# DMX_dimmer.net
KiCad netlist of a schematic drawn in EAGLE
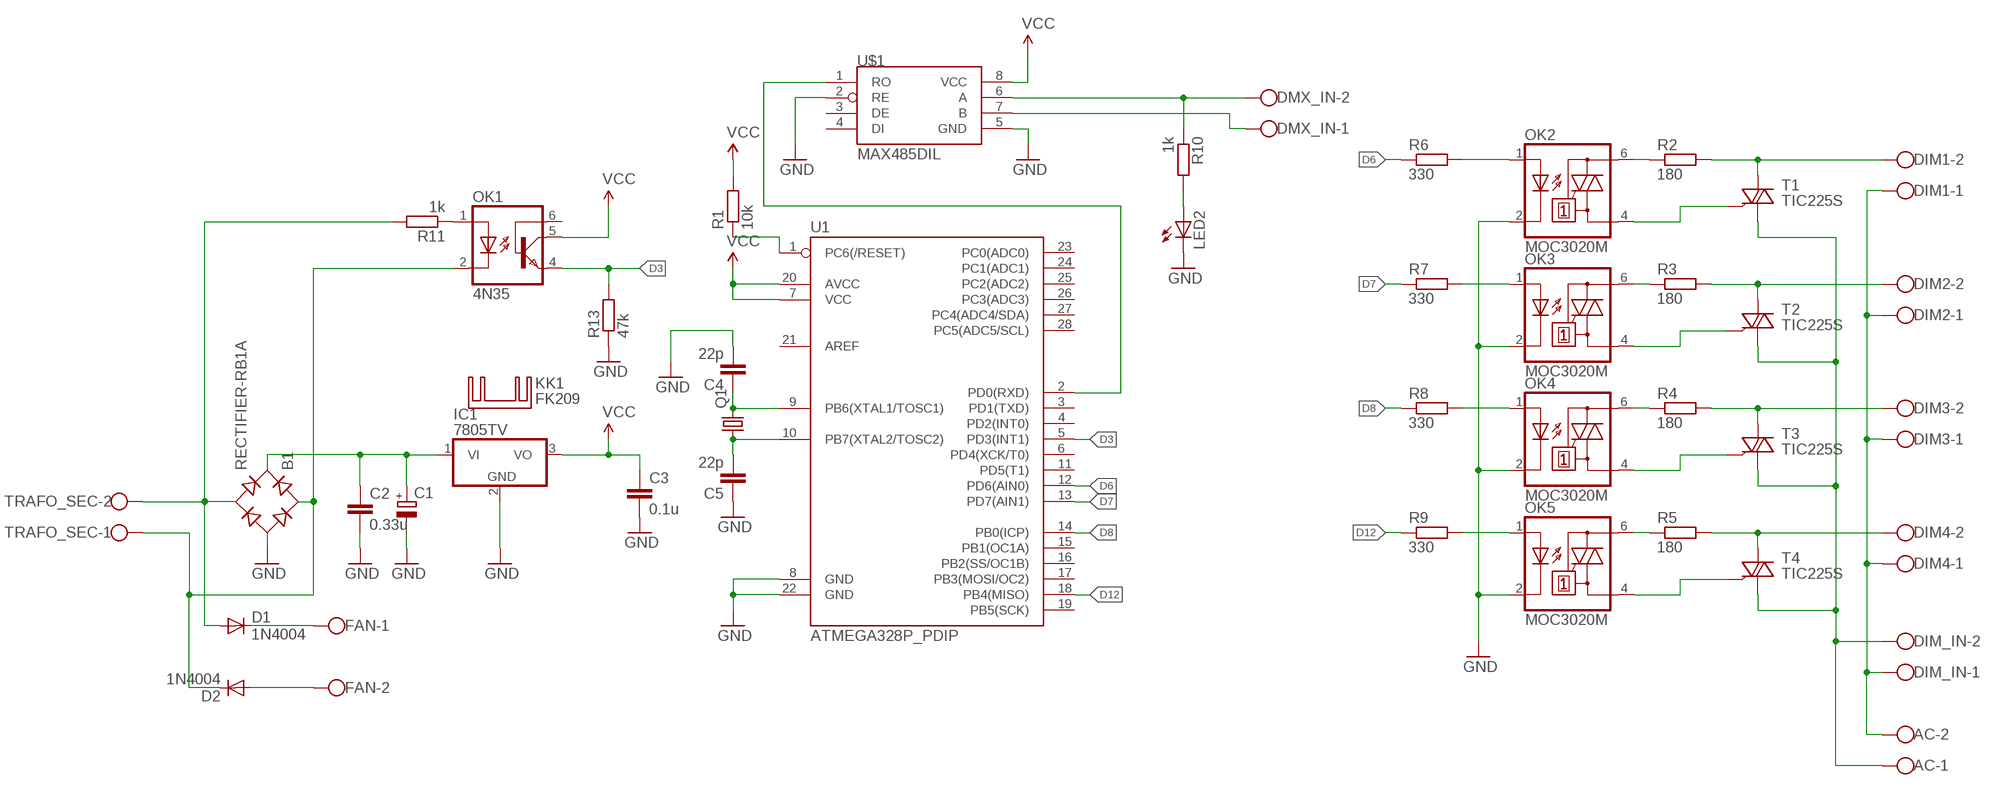
[diagram p0: schematic, sheet 1]

(export (version "E")
  (design (tool "Eeschema 10.0.6"))
  (components
    (comp (ref "AC")
      (value "W237-102")
      (footprint "eagle-import:W237-102")
      (fields (field (name "MPN") "237-102"))
      (libsource (lib "eagle-import") (part "W237-102"))
    )
    (comp (ref "B1")
      (value "RECTIFIER-RB1A")
      (footprint "eagle-import:RB1A")
      (libsource (lib "eagle-import") (part "RECTIFIER-RB1A"))
    )
    (comp (ref "C1")
      (value "CPOL-EUE5-10.5")
      (footprint "eagle-import:E5-10,5")
      (libsource (lib "eagle-import") (part "CPOL-EUE5-10.5"))
    )
    (comp (ref "C2")
      (value "0.33u")
      (footprint "eagle-import:C050-024X044")
      (libsource (lib "eagle-import") (part "C-EU050-024X044"))
    )
    (comp (ref "C3")
      (value "0.1u")
      (footprint "eagle-import:C050-024X044")
      (libsource (lib "eagle-import") (part "C-EU050-024X044"))
    )
    (comp (ref "C4")
      (value "22p")
      (footprint "eagle-import:C025-024X044")
      (libsource (lib "eagle-import") (part "C-EU025-024X044"))
    )
    (comp (ref "C5")
      (value "22p")
      (footprint "eagle-import:C025-024X044")
      (libsource (lib "eagle-import") (part "C-EU025-024X044"))
    )
    (comp (ref "D1")
      (value "1N4004")
      (footprint "eagle-import:DO41-10")
      (libsource (lib "eagle-import") (part "1N4004"))
    )
    (comp (ref "D2")
      (value "1N4004")
      (footprint "eagle-import:DO41-10")
      (libsource (lib "eagle-import") (part "1N4004"))
    )
    (comp (ref "DIM1")
      (value "W237-102")
      (footprint "eagle-import:W237-102")
      (fields (field (name "MPN") "237-102"))
      (libsource (lib "eagle-import") (part "W237-102"))
    )
    (comp (ref "DIM2")
      (value "W237-102")
      (footprint "eagle-import:W237-102")
      (fields (field (name "MPN") "237-102"))
      (libsource (lib "eagle-import") (part "W237-102"))
    )
    (comp (ref "DIM3")
      (value "W237-102")
      (footprint "eagle-import:W237-102")
      (fields (field (name "MPN") "237-102"))
      (libsource (lib "eagle-import") (part "W237-102"))
    )
    (comp (ref "DIM4")
      (value "W237-102")
      (footprint "eagle-import:W237-102")
      (fields (field (name "MPN") "237-102"))
      (libsource (lib "eagle-import") (part "W237-102"))
    )
    (comp (ref "DIM_IN")
      (value "W237-102")
      (footprint "eagle-import:W237-102")
      (fields (field (name "MPN") "237-102"))
      (libsource (lib "eagle-import") (part "W237-102"))
    )
    (comp (ref "DMX_IN")
      (value "W237-102")
      (footprint "eagle-import:W237-102")
      (fields (field (name "MPN") "237-102"))
      (libsource (lib "eagle-import") (part "W237-102"))
    )
    (comp (ref "FAN")
      (value "W237-102")
      (footprint "eagle-import:W237-102")
      (fields (field (name "MPN") "237-102"))
      (libsource (lib "eagle-import") (part "W237-102"))
    )
    (comp (ref "IC1")
      (value "7805TV")
      (footprint "eagle-import:TO220V")
      (libsource (lib "eagle-import") (part "78TV05"))
    )
    (comp (ref "KK1")
      (value "FK209")
      (footprint "eagle-import:FK209")
      (libsource (lib "eagle-import") (part "FK209"))
    )
    (comp (ref "LED2")
      (value "LED3MM")
      (footprint "eagle-import:LED3MM")
      (libsource (lib "eagle-import") (part "LED3MM"))
    )
    (comp (ref "OK1")
      (value "4N35")
      (footprint "eagle-import:DIL06")
      (fields (field (name "MF") "FAIRCHILD SEMICONDUCTOR"))
      (libsource (lib "eagle-import") (part "4N35"))
    )
    (comp (ref "OK2")
      (value "MOC3020M")
      (footprint "eagle-import:DIL06")
      (fields (field (name "MF") "FAIRCHILD SEMICONDUCTOR") (field (name "MPN") "MOC3020-M"))
      (libsource (lib "eagle-import") (part "MOC30M20"))
    )
    (comp (ref "OK3")
      (value "MOC3020M")
      (footprint "eagle-import:DIL06")
      (fields (field (name "MF") "FAIRCHILD SEMICONDUCTOR") (field (name "MPN") "MOC3020-M"))
      (libsource (lib "eagle-import") (part "MOC30M20"))
    )
    (comp (ref "OK4")
      (value "MOC3020M")
      (footprint "eagle-import:DIL06")
      (fields (field (name "MF") "FAIRCHILD SEMICONDUCTOR") (field (name "MPN") "MOC3020-M"))
      (libsource (lib "eagle-import") (part "MOC30M20"))
    )
    (comp (ref "OK5")
      (value "MOC3020M")
      (footprint "eagle-import:DIL06")
      (fields (field (name "MF") "FAIRCHILD SEMICONDUCTOR") (field (name "MPN") "MOC3020-M"))
      (libsource (lib "eagle-import") (part "MOC30M20"))
    )
    (comp (ref "Q1")
      (value "CRYSTALHC49U-V")
      (footprint "eagle-import:HC49U-V")
      (libsource (lib "eagle-import") (part "CRYSTALHC49U-V"))
    )
    (comp (ref "R1")
      (value "10k")
      (footprint "eagle-import:0207_7")
      (libsource (lib "eagle-import") (part "R-EU_0207/7"))
    )
    (comp (ref "R2")
      (value "180")
      (footprint "eagle-import:0207_2V")
      (libsource (lib "eagle-import") (part "R-EU_0207/2V"))
    )
    (comp (ref "R3")
      (value "180")
      (footprint "eagle-import:0207_2V")
      (libsource (lib "eagle-import") (part "R-EU_0207/2V"))
    )
    (comp (ref "R4")
      (value "180")
      (footprint "eagle-import:0207_2V")
      (libsource (lib "eagle-import") (part "R-EU_0207/2V"))
    )
    (comp (ref "R5")
      (value "180")
      (footprint "eagle-import:0207_2V")
      (libsource (lib "eagle-import") (part "R-EU_0207/2V"))
    )
    (comp (ref "R6")
      (value "330")
      (footprint "eagle-import:0207_7")
      (libsource (lib "eagle-import") (part "R-EU_0207/7"))
    )
    (comp (ref "R7")
      (value "330")
      (footprint "eagle-import:0207_7")
      (libsource (lib "eagle-import") (part "R-EU_0207/7"))
    )
    (comp (ref "R8")
      (value "330")
      (footprint "eagle-import:0207_7")
      (libsource (lib "eagle-import") (part "R-EU_0207/7"))
    )
    (comp (ref "R9")
      (value "330")
      (footprint "eagle-import:0207_7")
      (libsource (lib "eagle-import") (part "R-EU_0207/7"))
    )
    (comp (ref "R10")
      (value "1k")
      (footprint "eagle-import:0207_7")
      (libsource (lib "eagle-import") (part "R-EU_0207/7"))
    )
    (comp (ref "R11")
      (value "1k")
      (footprint "eagle-import:0207_7")
      (libsource (lib "eagle-import") (part "R-EU_0207/7"))
    )
    (comp (ref "R13")
      (value "47k")
      (footprint "eagle-import:0207_7")
      (libsource (lib "eagle-import") (part "R-EU_0207/7"))
    )
    (comp (ref "T1")
      (value "TIC225S")
      (footprint "eagle-import:TO220DS")
      (libsource (lib "eagle-import") (part "TIC225S"))
    )
    (comp (ref "T2")
      (value "TIC225S")
      (footprint "eagle-import:TO220DS")
      (libsource (lib "eagle-import") (part "TIC225S"))
    )
    (comp (ref "T3")
      (value "TIC225S")
      (footprint "eagle-import:TO220DS")
      (libsource (lib "eagle-import") (part "TIC225S"))
    )
    (comp (ref "T4")
      (value "TIC225S")
      (footprint "eagle-import:TO220DS")
      (libsource (lib "eagle-import") (part "TIC225S"))
    )
    (comp (ref "TRAFO_SEC")
      (value "W237-102")
      (footprint "eagle-import:W237-102")
      (fields (field (name "MPN") "237-102"))
      (libsource (lib "eagle-import") (part "W237-102"))
    )
    (comp (ref "U$1")
      (value "MAX485DIL")
      (footprint "eagle-import:DIL08")
      (libsource (lib "eagle-import") (part "MAX485DIL"))
    )
    (comp (ref "U1")
      (value "ATMEGA328P_PDIP")
      (footprint "eagle-import:DIL28-3")
      (libsource (lib "eagle-import") (part "ATMEGA328P_PDIP"))
    )
  )
  (nets
    (net (code "1") (name "D3") (class "Default")
      (node (ref "OK1") (pin "4") (pinfunction "EMI_4") (pintype "passive"))
      (node (ref "R13") (pin "2") (pinfunction "2_2") (pintype "passive"))
      (node (ref "U1") (pin "5") (pinfunction "PD3(INT1)_5") (pintype "bidirectional"))
    )
    (net (code "2") (name "D6") (class "Default")
      (node (ref "R6") (pin "1") (pinfunction "1_1") (pintype "passive"))
      (node (ref "U1") (pin "12") (pinfunction "PD6(AIN0)_12") (pintype "bidirectional"))
    )
    (net (code "3") (name "D7") (class "Default")
      (node (ref "R7") (pin "1") (pinfunction "1_1") (pintype "passive"))
      (node (ref "U1") (pin "13") (pinfunction "PD7(AIN1)_13") (pintype "bidirectional"))
    )
    (net (code "4") (name "D8") (class "Default")
      (node (ref "R8") (pin "1") (pinfunction "1_1") (pintype "passive"))
      (node (ref "U1") (pin "14") (pinfunction "PB0(ICP)_14") (pintype "bidirectional"))
    )
    (net (code "5") (name "D12") (class "Default")
      (node (ref "R9") (pin "1") (pinfunction "1_1") (pintype "passive"))
      (node (ref "U1") (pin "18") (pinfunction "PB4(MISO)_18") (pintype "bidirectional"))
    )
    (net (code "6") (name "GND") (class "Default")
      (node (ref "B1") (pin "-") (pinfunction "-_-") (pintype "passive"))
      (node (ref "C1") (pin "-") (pinfunction "-_-") (pintype "passive"))
      (node (ref "C2") (pin "2") (pinfunction "2_2") (pintype "passive"))
      (node (ref "C3") (pin "2") (pinfunction "2_2") (pintype "passive"))
      (node (ref "C4") (pin "2") (pinfunction "2_2") (pintype "passive"))
      (node (ref "C5") (pin "1") (pinfunction "1_1") (pintype "passive"))
      (node (ref "IC1") (pin "2") (pinfunction "GND_2") (pintype "passive"))
      (node (ref "LED2") (pin "K") (pinfunction "C_K") (pintype "passive"))
      (node (ref "OK2") (pin "2") (pinfunction "C_2") (pintype "passive"))
      (node (ref "OK3") (pin "2") (pinfunction "C_2") (pintype "passive"))
      (node (ref "OK4") (pin "2") (pinfunction "C_2") (pintype "passive"))
      (node (ref "OK5") (pin "2") (pinfunction "C_2") (pintype "passive"))
      (node (ref "R13") (pin "1") (pinfunction "1_1") (pintype "passive"))
      (node (ref "U$1") (pin "2") (pinfunction "RE_2") (pintype "bidirectional"))
      (node (ref "U$1") (pin "5") (pinfunction "GND_5") (pintype "bidirectional"))
      (node (ref "U1") (pin "22") (pinfunction "GND_22") (pintype "bidirectional"))
      (node (ref "U1") (pin "8") (pinfunction "GND_8") (pintype "bidirectional"))
    )
    (net (code "7") (name "Net-(ACA-KL)") (class "Default")
      (node (ref "AC") (pin "1") (pinfunction "KL_1") (pintype "passive"))
      (node (ref "DIM_IN") (pin "2") (pinfunction "KL_2") (pintype "passive"))
      (node (ref "T1") (pin "A1") (pinfunction "A1_A1") (pintype "passive"))
      (node (ref "T2") (pin "A1") (pinfunction "A1_A1") (pintype "passive"))
      (node (ref "T3") (pin "A1") (pinfunction "A1_A1") (pintype "passive"))
      (node (ref "T4") (pin "A1") (pinfunction "A1_A1") (pintype "passive"))
    )
    (net (code "8") (name "Net-(ACB-KL)") (class "Default")
      (node (ref "AC") (pin "2") (pinfunction "KL_2") (pintype "passive"))
      (node (ref "DIM1") (pin "1") (pinfunction "KL_1") (pintype "passive"))
      (node (ref "DIM2") (pin "1") (pinfunction "KL_1") (pintype "passive"))
      (node (ref "DIM3") (pin "1") (pinfunction "KL_1") (pintype "passive"))
      (node (ref "DIM4") (pin "1") (pinfunction "KL_1") (pintype "passive"))
      (node (ref "DIM_IN") (pin "1") (pinfunction "KL_1") (pintype "passive"))
    )
    (net (code "9") (name "Net-(DIM1B-KL)") (class "Default")
      (node (ref "DIM1") (pin "2") (pinfunction "KL_2") (pintype "passive"))
      (node (ref "R2") (pin "2") (pinfunction "2_2") (pintype "passive"))
      (node (ref "T1") (pin "A2") (pinfunction "A2_A2") (pintype "passive"))
    )
    (net (code "10") (name "Net-(DIM2B-KL)") (class "Default")
      (node (ref "DIM2") (pin "2") (pinfunction "KL_2") (pintype "passive"))
      (node (ref "R3") (pin "2") (pinfunction "2_2") (pintype "passive"))
      (node (ref "T2") (pin "A2") (pinfunction "A2_A2") (pintype "passive"))
    )
    (net (code "11") (name "Net-(DIM3B-KL)") (class "Default")
      (node (ref "DIM3") (pin "2") (pinfunction "KL_2") (pintype "passive"))
      (node (ref "R4") (pin "2") (pinfunction "2_2") (pintype "passive"))
      (node (ref "T3") (pin "A2") (pinfunction "A2_A2") (pintype "passive"))
    )
    (net (code "12") (name "Net-(DIM4B-KL)") (class "Default")
      (node (ref "DIM4") (pin "2") (pinfunction "KL_2") (pintype "passive"))
      (node (ref "R5") (pin "2") (pinfunction "2_2") (pintype "passive"))
      (node (ref "T4") (pin "A2") (pinfunction "A2_A2") (pintype "passive"))
    )
    (net (code "13") (name "Net-(DMX_INA-KL)") (class "Default")
      (node (ref "DMX_IN") (pin "1") (pinfunction "KL_1") (pintype "passive"))
      (node (ref "U$1") (pin "7") (pinfunction "B_7") (pintype "bidirectional"))
    )
    (net (code "14") (name "Net-(DMX_INB-KL)") (class "Default")
      (node (ref "DMX_IN") (pin "2") (pinfunction "KL_2") (pintype "passive"))
      (node (ref "R10") (pin "1") (pinfunction "1_1") (pintype "passive"))
      (node (ref "U$1") (pin "6") (pinfunction "A_6") (pintype "bidirectional"))
    )
    (net (code "15") (name "Net-(FANA-KL)") (class "Default")
      (node (ref "D1") (pin "C") (pinfunction "C_C") (pintype "passive"))
      (node (ref "FAN") (pin "1") (pinfunction "KL_1") (pintype "passive"))
    )
    (net (code "16") (name "Net-(FANB-KL)") (class "Default")
      (node (ref "D2") (pin "A") (pinfunction "A_A") (pintype "passive"))
      (node (ref "FAN") (pin "2") (pinfunction "KL_2") (pintype "passive"))
    )
    (net (code "17") (name "Net-(IC1-VI)") (class "Default")
      (node (ref "B1") (pin "+") (pinfunction "+_+") (pintype "passive"))
      (node (ref "C1") (pin "+") (pinfunction "+_+") (pintype "passive"))
      (node (ref "C2") (pin "1") (pinfunction "1_1") (pintype "passive"))
      (node (ref "IC1") (pin "1") (pinfunction "VI_1") (pintype "input"))
    )
    (net (code "18") (name "Net-(LED2-PadA)") (class "Default")
      (node (ref "LED2") (pin "A") (pinfunction "A_A") (pintype "passive"))
      (node (ref "R10") (pin "2") (pinfunction "2_2") (pintype "passive"))
    )
    (net (code "19") (name "Net-(OK1-A)") (class "Default")
      (node (ref "OK1") (pin "1") (pinfunction "A_1") (pintype "passive"))
      (node (ref "R11") (pin "1") (pinfunction "1_1") (pintype "passive"))
    )
    (net (code "20") (name "Net-(OK1-C)") (class "Default")
      (node (ref "B1") (pin "AC1") (pinfunction "AC1_AC1") (pintype "passive"))
      (node (ref "D2") (pin "C") (pinfunction "C_C") (pintype "passive"))
      (node (ref "OK1") (pin "2") (pinfunction "C_2") (pintype "passive"))
      (node (ref "TRAFO_SEC") (pin "1") (pinfunction "KL_1") (pintype "passive"))
    )
    (net (code "21") (name "Net-(OK2-A)") (class "Default")
      (node (ref "OK2") (pin "1") (pinfunction "A_1") (pintype "passive"))
      (node (ref "R6") (pin "2") (pinfunction "2_2") (pintype "passive"))
    )
    (net (code "22") (name "Net-(OK2-A1)") (class "Default")
      (node (ref "OK2") (pin "4") (pinfunction "A1_4") (pintype "passive"))
      (node (ref "T1") (pin "G") (pinfunction "G_G") (pintype "passive"))
    )
    (net (code "23") (name "Net-(OK2-A2)") (class "Default")
      (node (ref "OK2") (pin "6") (pinfunction "A2_6") (pintype "passive"))
      (node (ref "R2") (pin "1") (pinfunction "1_1") (pintype "passive"))
    )
    (net (code "24") (name "Net-(OK3-A)") (class "Default")
      (node (ref "OK3") (pin "1") (pinfunction "A_1") (pintype "passive"))
      (node (ref "R7") (pin "2") (pinfunction "2_2") (pintype "passive"))
    )
    (net (code "25") (name "Net-(OK3-A1)") (class "Default")
      (node (ref "OK3") (pin "4") (pinfunction "A1_4") (pintype "passive"))
      (node (ref "T2") (pin "G") (pinfunction "G_G") (pintype "passive"))
    )
    (net (code "26") (name "Net-(OK3-A2)") (class "Default")
      (node (ref "OK3") (pin "6") (pinfunction "A2_6") (pintype "passive"))
      (node (ref "R3") (pin "1") (pinfunction "1_1") (pintype "passive"))
    )
    (net (code "27") (name "Net-(OK4-A)") (class "Default")
      (node (ref "OK4") (pin "1") (pinfunction "A_1") (pintype "passive"))
      (node (ref "R8") (pin "2") (pinfunction "2_2") (pintype "passive"))
    )
    (net (code "28") (name "Net-(OK4-A1)") (class "Default")
      (node (ref "OK4") (pin "4") (pinfunction "A1_4") (pintype "passive"))
      (node (ref "T3") (pin "G") (pinfunction "G_G") (pintype "passive"))
    )
    (net (code "29") (name "Net-(OK4-A2)") (class "Default")
      (node (ref "OK4") (pin "6") (pinfunction "A2_6") (pintype "passive"))
      (node (ref "R4") (pin "1") (pinfunction "1_1") (pintype "passive"))
    )
    (net (code "30") (name "Net-(OK5-A)") (class "Default")
      (node (ref "OK5") (pin "1") (pinfunction "A_1") (pintype "passive"))
      (node (ref "R9") (pin "2") (pinfunction "2_2") (pintype "passive"))
    )
    (net (code "31") (name "Net-(OK5-A1)") (class "Default")
      (node (ref "OK5") (pin "4") (pinfunction "A1_4") (pintype "passive"))
      (node (ref "T4") (pin "G") (pinfunction "G_G") (pintype "passive"))
    )
    (net (code "32") (name "Net-(OK5-A2)") (class "Default")
      (node (ref "OK5") (pin "6") (pinfunction "A2_6") (pintype "passive"))
      (node (ref "R5") (pin "1") (pinfunction "1_1") (pintype "passive"))
    )
    (net (code "33") (name "Net-(TRAFO_SECB-KL)") (class "Default")
      (node (ref "B1") (pin "AC2") (pinfunction "AC2_AC2") (pintype "passive"))
      (node (ref "D1") (pin "A") (pinfunction "A_A") (pintype "passive"))
      (node (ref "R11") (pin "2") (pinfunction "2_2") (pintype "passive"))
      (node (ref "TRAFO_SEC") (pin "2") (pinfunction "KL_2") (pintype "passive"))
    )
    (net (code "34") (name "Net-(U$1-RO)") (class "Default")
      (node (ref "U$1") (pin "1") (pinfunction "RO_1") (pintype "bidirectional"))
      (node (ref "U1") (pin "2") (pinfunction "PD0(RXD)_2") (pintype "bidirectional"))
    )
    (net (code "35") (name "Net-(U1-PB6(XTAL1{slash}TOSC1))") (class "Default")
      (node (ref "C4") (pin "1") (pinfunction "1_1") (pintype "passive"))
      (node (ref "Q1") (pin "2") (pinfunction "2_2") (pintype "passive"))
      (node (ref "U1") (pin "9") (pinfunction "PB6(XTAL1/TOSC1)_9") (pintype "bidirectional"))
    )
    (net (code "36") (name "Net-(U1-PB7(XTAL2{slash}TOSC2))") (class "Default")
      (node (ref "C5") (pin "2") (pinfunction "2_2") (pintype "passive"))
      (node (ref "Q1") (pin "1") (pinfunction "1_1") (pintype "passive"))
      (node (ref "U1") (pin "10") (pinfunction "PB7(XTAL2/TOSC2)_10") (pintype "bidirectional"))
    )
    (net (code "37") (name "Net-(U1-PC6({slash}RESET))") (class "Default")
      (node (ref "R1") (pin "1") (pinfunction "1_1") (pintype "passive"))
      (node (ref "U1") (pin "1") (pinfunction "PC6(/RESET)_1") (pintype "bidirectional"))
    )
    (net (code "38") (name "VCC") (class "Default")
      (node (ref "C3") (pin "1") (pinfunction "1_1") (pintype "passive"))
      (node (ref "IC1") (pin "3") (pinfunction "VO_3") (pintype "passive"))
      (node (ref "OK1") (pin "5") (pinfunction "COL_5") (pintype "passive"))
      (node (ref "R1") (pin "2") (pinfunction "2_2") (pintype "passive"))
      (node (ref "U$1") (pin "8") (pinfunction "VCC_8") (pintype "bidirectional"))
      (node (ref "U1") (pin "20") (pinfunction "AVCC_20") (pintype "bidirectional"))
      (node (ref "U1") (pin "7") (pinfunction "VCC_7") (pintype "bidirectional"))
    )
    (net (code "39") (name "unconnected-(OK1-BAS-Pad6)") (class "Default")
      (node (ref "OK1") (pin "6") (pinfunction "BAS_6") (pintype "passive"))
    )
    (net (code "40") (name "unconnected-(U$1-DE-Pad3)") (class "Default")
      (node (ref "U$1") (pin "3") (pinfunction "DE_3") (pintype "bidirectional"))
    )
    (net (code "41") (name "unconnected-(U$1-DI-Pad4)") (class "Default")
      (node (ref "U$1") (pin "4") (pinfunction "DI_4") (pintype "bidirectional"))
    )
    (net (code "42") (name "unconnected-(U1-AREF-Pad21)") (class "Default")
      (node (ref "U1") (pin "21") (pinfunction "AREF_21") (pintype "bidirectional"))
    )
    (net (code "43") (name "unconnected-(U1-PB1(OC1A)-Pad15)") (class "Default")
      (node (ref "U1") (pin "15") (pinfunction "PB1(OC1A)_15") (pintype "bidirectional"))
    )
    (net (code "44") (name "unconnected-(U1-PB2(SS{slash}OC1B)-Pad16)") (class "Default")
      (node (ref "U1") (pin "16") (pinfunction "PB2(SS/OC1B)_16") (pintype "bidirectional"))
    )
    (net (code "45") (name "unconnected-(U1-PB3(MOSI{slash}OC2)-Pad17)") (class "Default")
      (node (ref "U1") (pin "17") (pinfunction "PB3(MOSI/OC2)_17") (pintype "bidirectional"))
    )
    (net (code "46") (name "unconnected-(U1-PB5(SCK)-Pad19)") (class "Default")
      (node (ref "U1") (pin "19") (pinfunction "PB5(SCK)_19") (pintype "bidirectional"))
    )
    (net (code "47") (name "unconnected-(U1-PC0(ADC0)-Pad23)") (class "Default")
      (node (ref "U1") (pin "23") (pinfunction "PC0(ADC0)_23") (pintype "bidirectional"))
    )
    (net (code "48") (name "unconnected-(U1-PC1(ADC1)-Pad24)") (class "Default")
      (node (ref "U1") (pin "24") (pinfunction "PC1(ADC1)_24") (pintype "bidirectional"))
    )
    (net (code "49") (name "unconnected-(U1-PC2(ADC2)-Pad25)") (class "Default")
      (node (ref "U1") (pin "25") (pinfunction "PC2(ADC2)_25") (pintype "bidirectional"))
    )
    (net (code "50") (name "unconnected-(U1-PC3(ADC3)-Pad26)") (class "Default")
      (node (ref "U1") (pin "26") (pinfunction "PC3(ADC3)_26") (pintype "bidirectional"))
    )
    (net (code "51") (name "unconnected-(U1-PC4(ADC4{slash}SDA)-Pad27)") (class "Default")
      (node (ref "U1") (pin "27") (pinfunction "PC4(ADC4/SDA)_27") (pintype "bidirectional"))
    )
    (net (code "52") (name "unconnected-(U1-PC5(ADC5{slash}SCL)-Pad28)") (class "Default")
      (node (ref "U1") (pin "28") (pinfunction "PC5(ADC5/SCL)_28") (pintype "bidirectional"))
    )
    (net (code "53") (name "unconnected-(U1-PD1(TXD)-Pad3)") (class "Default")
      (node (ref "U1") (pin "3") (pinfunction "PD1(TXD)_3") (pintype "bidirectional"))
    )
    (net (code "54") (name "unconnected-(U1-PD2(INT0)-Pad4)") (class "Default")
      (node (ref "U1") (pin "4") (pinfunction "PD2(INT0)_4") (pintype "bidirectional"))
    )
    (net (code "55") (name "unconnected-(U1-PD4(XCK{slash}T0)-Pad6)") (class "Default")
      (node (ref "U1") (pin "6") (pinfunction "PD4(XCK/T0)_6") (pintype "bidirectional"))
    )
    (net (code "56") (name "unconnected-(U1-PD5(T1)-Pad11)") (class "Default")
      (node (ref "U1") (pin "11") (pinfunction "PD5(T1)_11") (pintype "bidirectional"))
    )
  )
)
